# Digital_Trimmers.net
KiCad netlist of a schematic drawn in Altium Designer
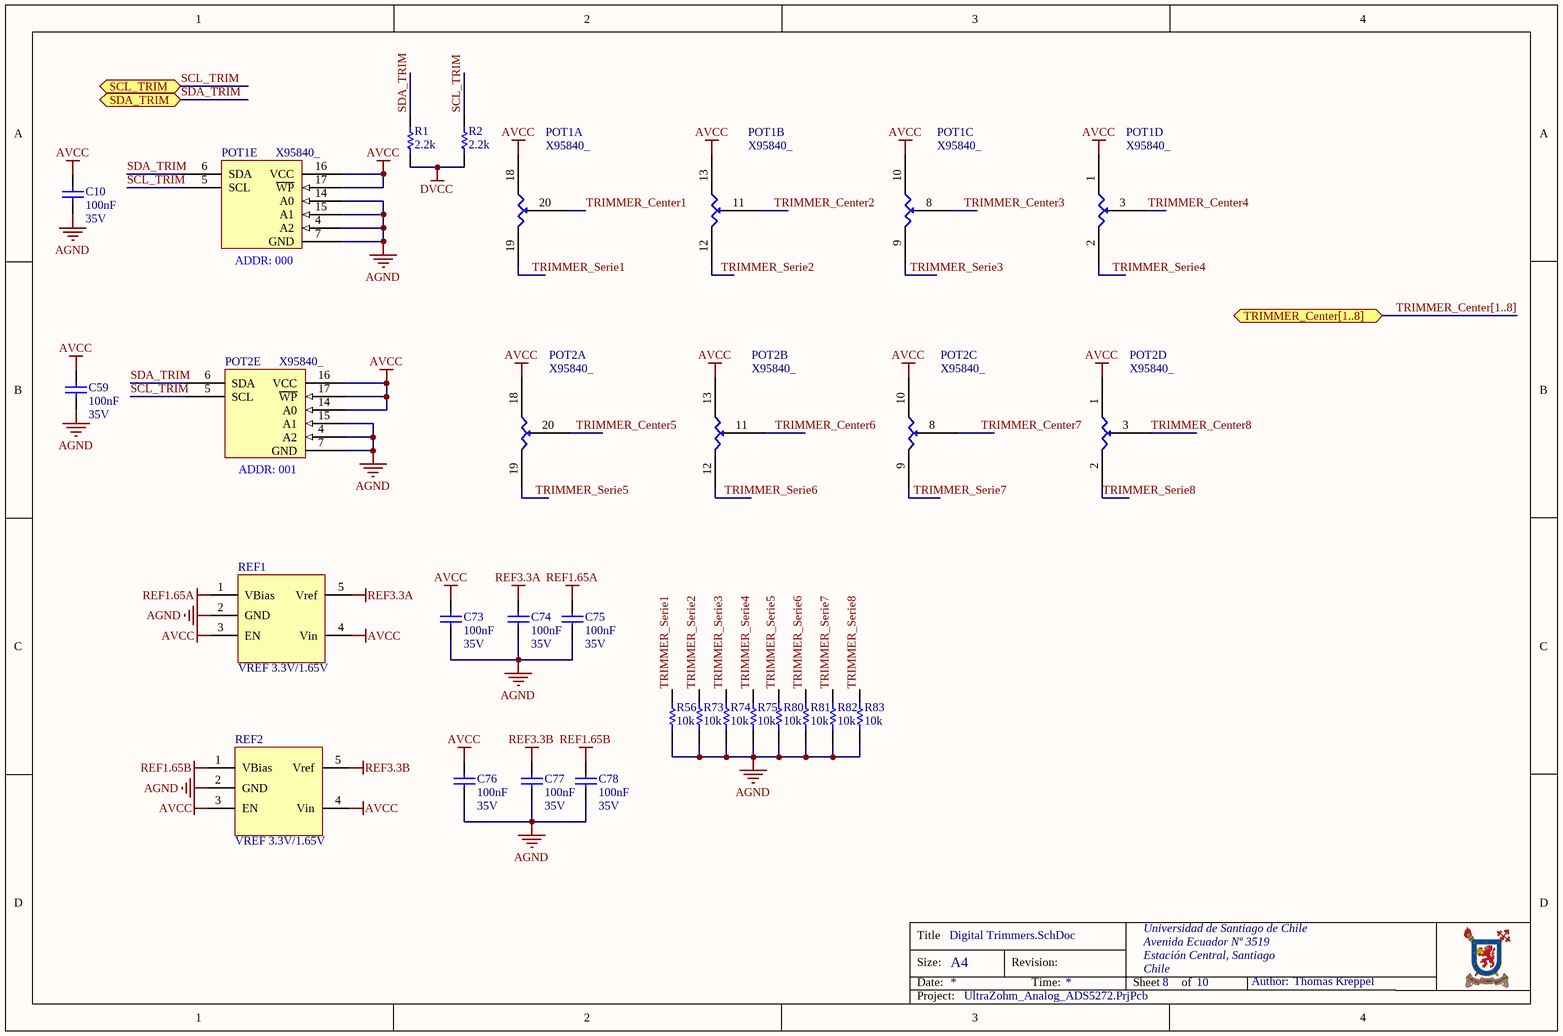
[diagram p0: Digital Trimmers.SchDoc]

(export (version "E")
  (design (tool "Eeschema 10.0.6"))
  (components
    (comp (ref "C10")
      (value "100nF")
      (footprint "CAP_0603")
      (description "Capacitor")
      (fields
        (field (name "MPN") "C0603C104M5RACTU")
        (field (name "MF") "KEMET")
        (field (name "VOLTAGE") "35V")
        (field (name "PUBLISHER") "Altium Limited")
      )
      (libsource (lib "Componentes_SOC") (part "Cap_0603"))
    )
    (comp (ref "C59")
      (value "100nF")
      (footprint "CAP_0603")
      (description "Capacitor")
      (fields
        (field (name "MPN") "C0603C104M5RACTU")
        (field (name "MF") "KEMET")
        (field (name "VOLTAGE") "35V")
        (field (name "PUBLISHER") "Altium Limited")
      )
      (libsource (lib "Componentes_SOC") (part "Cap_0603"))
    )
    (comp (ref "C73")
      (value "100nF")
      (footprint "CAP_0603")
      (description "Capacitor")
      (fields
        (field (name "MPN") "C0603C104M5RACTU")
        (field (name "MF") "KEMET")
        (field (name "VOLTAGE") "35V")
        (field (name "PUBLISHER") "Altium Limited")
      )
      (libsource (lib "Componentes_SOC") (part "Cap_0603"))
    )
    (comp (ref "C74")
      (value "100nF")
      (footprint "CAP_0603")
      (description "Capacitor")
      (fields
        (field (name "MPN") "C0603C104M5RACTU")
        (field (name "MF") "KEMET")
        (field (name "VOLTAGE") "35V")
        (field (name "PUBLISHER") "Altium Limited")
      )
      (libsource (lib "Componentes_SOC") (part "Cap_0603"))
    )
    (comp (ref "C75")
      (value "100nF")
      (footprint "CAP_0603")
      (description "Capacitor")
      (fields
        (field (name "MPN") "C0603C104M5RACTU")
        (field (name "MF") "KEMET")
        (field (name "VOLTAGE") "35V")
        (field (name "PUBLISHER") "Altium Limited")
      )
      (libsource (lib "Componentes_SOC") (part "Cap_0603"))
    )
    (comp (ref "C76")
      (value "100nF")
      (footprint "CAP_0603")
      (description "Capacitor")
      (fields
        (field (name "MPN") "C0603C104M5RACTU")
        (field (name "MF") "KEMET")
        (field (name "VOLTAGE") "35V")
        (field (name "PUBLISHER") "Altium Limited")
      )
      (libsource (lib "Componentes_SOC") (part "Cap_0603"))
    )
    (comp (ref "C77")
      (value "100nF")
      (footprint "CAP_0603")
      (description "Capacitor")
      (fields
        (field (name "MPN") "C0603C104M5RACTU")
        (field (name "MF") "KEMET")
        (field (name "VOLTAGE") "35V")
        (field (name "PUBLISHER") "Altium Limited")
      )
      (libsource (lib "Componentes_SOC") (part "Cap_0603"))
    )
    (comp (ref "C78")
      (value "100nF")
      (footprint "CAP_0603")
      (description "Capacitor")
      (fields
        (field (name "MPN") "C0603C104M5RACTU")
        (field (name "MF") "KEMET")
        (field (name "VOLTAGE") "35V")
        (field (name "PUBLISHER") "Altium Limited")
      )
      (libsource (lib "Componentes_SOC") (part "Cap_0603"))
    )
    (comp (ref "POT1")
      (value "X95840_")
      (footprint "TSSO6X6-G20/D6.6")
      (description "Digital Trimmer")
      (fields (field (name "MPN") "X95840WV20IZ-2.7") (field (name "MF") "Renesas Electronics"))
      (libsource (lib "Componentes_SOC") (part "X95840_"))
    )
    (comp (ref "POT2")
      (value "X95840_")
      (footprint "TSSO6X6-G20/D6.6")
      (description "Digital Trimmer")
      (fields (field (name "MPN") "X95840WV20IZ-2.7") (field (name "MF") "Renesas Electronics"))
      (libsource (lib "Componentes_SOC") (part "X95840_"))
    )
    (comp (ref "R1")
      (value "2.2k")
      (footprint "RES_0603")
      (fields
        (field (name "MPN") "RC0603FR-072K2L")
        (field (name "TOLERANCE") "1%")
        (field (name "PUBLISHER") "Altium Limited")
      )
      (libsource (lib "Componentes_SOC") (part "Res0603"))
    )
    (comp (ref "R2")
      (value "2.2k")
      (footprint "RES_0603")
      (fields
        (field (name "MPN") "RC0603FR-072K2L")
        (field (name "TOLERANCE") "1%")
        (field (name "PUBLISHER") "Altium Limited")
      )
      (libsource (lib "Componentes_SOC") (part "Res0603"))
    )
    (comp (ref "R56")
      (value "10k")
      (footprint "RES_0603")
      (fields (field (name "TOLERANCE") "1%") (field (name "PUBLISHER") "Altium Limited"))
      (libsource (lib "Componentes_SOC") (part "Res0603"))
    )
    (comp (ref "R73")
      (value "10k")
      (footprint "RES_0603")
      (fields (field (name "TOLERANCE") "1%") (field (name "PUBLISHER") "Altium Limited"))
      (libsource (lib "Componentes_SOC") (part "Res0603"))
    )
    (comp (ref "R74")
      (value "10k")
      (footprint "RES_0603")
      (fields (field (name "TOLERANCE") "1%") (field (name "PUBLISHER") "Altium Limited"))
      (libsource (lib "Componentes_SOC") (part "Res0603"))
    )
    (comp (ref "R75")
      (value "10k")
      (footprint "RES_0603")
      (fields (field (name "TOLERANCE") "1%") (field (name "PUBLISHER") "Altium Limited"))
      (libsource (lib "Componentes_SOC") (part "Res0603"))
    )
    (comp (ref "R80")
      (value "10k")
      (footprint "RES_0603")
      (fields (field (name "TOLERANCE") "1%") (field (name "PUBLISHER") "Altium Limited"))
      (libsource (lib "Componentes_SOC") (part "Res0603"))
    )
    (comp (ref "R81")
      (value "10k")
      (footprint "RES_0603")
      (fields (field (name "TOLERANCE") "1%") (field (name "PUBLISHER") "Altium Limited"))
      (libsource (lib "Componentes_SOC") (part "Res0603"))
    )
    (comp (ref "R82")
      (value "10k")
      (footprint "RES_0603")
      (fields (field (name "TOLERANCE") "1%") (field (name "PUBLISHER") "Altium Limited"))
      (libsource (lib "Componentes_SOC") (part "Res0603"))
    )
    (comp (ref "R83")
      (value "10k")
      (footprint "RES_0603")
      (fields (field (name "TOLERANCE") "1%") (field (name "PUBLISHER") "Altium Limited"))
      (libsource (lib "Componentes_SOC") (part "Res0603"))
    )
    (comp (ref "REF1")
      (value "VREF 3.3V/1.65V")
      (footprint "SOT-23-5")
      (libsource (lib "Componentes_SOC") (part "VREF 3.3V/1.65V"))
    )
    (comp (ref "REF2")
      (value "VREF 3.3V/1.65V")
      (footprint "SOT-23-5")
      (libsource (lib "Componentes_SOC") (part "VREF 3.3V/1.65V"))
    )
  )
  (nets
    (net (code "1") (name "/SCL_TRIM") (class "Default")
      (node (ref "POT1") (pin "5") (pinfunction "SCL_5") (pintype "passive"))
      (node (ref "POT2") (pin "5") (pinfunction "SCL_5") (pintype "passive"))
      (node (ref "R2") (pin "2") (pinfunction "2_2") (pintype "passive"))
    )
    (net (code "2") (name "/SDA_TRIM") (class "Default")
      (node (ref "POT1") (pin "6") (pinfunction "SDA_6") (pintype "passive"))
      (node (ref "POT2") (pin "6") (pinfunction "SDA_6") (pintype "passive"))
      (node (ref "R1") (pin "2") (pinfunction "2_2") (pintype "passive"))
    )
    (net (code "3") (name "/TRIMMER_Center1") (class "Default")
      (node (ref "POT1") (pin "20") (pinfunction "20_20") (pintype "passive"))
    )
    (net (code "4") (name "/TRIMMER_Center2") (class "Default")
      (node (ref "POT1") (pin "11") (pinfunction "RW1_11") (pintype "passive"))
    )
    (net (code "5") (name "/TRIMMER_Center3") (class "Default")
      (node (ref "POT1") (pin "8") (pinfunction "RW2_8") (pintype "passive"))
    )
    (net (code "6") (name "/TRIMMER_Center4") (class "Default")
      (node (ref "POT1") (pin "3") (pinfunction "RW3_3") (pintype "passive"))
    )
    (net (code "7") (name "/TRIMMER_Center5") (class "Default")
      (node (ref "POT2") (pin "20") (pinfunction "20_20") (pintype "passive"))
    )
    (net (code "8") (name "/TRIMMER_Center6") (class "Default")
      (node (ref "POT2") (pin "11") (pinfunction "RW1_11") (pintype "passive"))
    )
    (net (code "9") (name "/TRIMMER_Center7") (class "Default")
      (node (ref "POT2") (pin "8") (pinfunction "RW2_8") (pintype "passive"))
    )
    (net (code "10") (name "/TRIMMER_Center8") (class "Default")
      (node (ref "POT2") (pin "3") (pinfunction "RW3_3") (pintype "passive"))
    )
    (net (code "12") (name "/TRIMMER_Serie1") (class "Default")
      (node (ref "POT1") (pin "19") (pinfunction "19_19") (pintype "passive"))
      (node (ref "R56") (pin "2") (pinfunction "2_2") (pintype "passive"))
    )
    (net (code "13") (name "/TRIMMER_Serie2") (class "Default")
      (node (ref "POT1") (pin "12") (pinfunction "RL1_12") (pintype "passive"))
      (node (ref "R73") (pin "2") (pinfunction "2_2") (pintype "passive"))
    )
    (net (code "14") (name "/TRIMMER_Serie3") (class "Default")
      (node (ref "POT1") (pin "9") (pinfunction "RL2_9") (pintype "passive"))
      (node (ref "R74") (pin "2") (pinfunction "2_2") (pintype "passive"))
    )
    (net (code "15") (name "/TRIMMER_Serie4") (class "Default")
      (node (ref "POT1") (pin "2") (pinfunction "RL3_2") (pintype "passive"))
      (node (ref "R75") (pin "2") (pinfunction "2_2") (pintype "passive"))
    )
    (net (code "16") (name "/TRIMMER_Serie5") (class "Default")
      (node (ref "POT2") (pin "19") (pinfunction "19_19") (pintype "passive"))
      (node (ref "R80") (pin "2") (pinfunction "2_2") (pintype "passive"))
    )
    (net (code "17") (name "/TRIMMER_Serie6") (class "Default")
      (node (ref "POT2") (pin "12") (pinfunction "RL1_12") (pintype "passive"))
      (node (ref "R81") (pin "2") (pinfunction "2_2") (pintype "passive"))
    )
    (net (code "18") (name "/TRIMMER_Serie7") (class "Default")
      (node (ref "POT2") (pin "9") (pinfunction "RL2_9") (pintype "passive"))
      (node (ref "R82") (pin "2") (pinfunction "2_2") (pintype "passive"))
    )
    (net (code "19") (name "/TRIMMER_Serie8") (class "Default")
      (node (ref "POT2") (pin "2") (pinfunction "RL3_2") (pintype "passive"))
      (node (ref "R83") (pin "2") (pinfunction "2_2") (pintype "passive"))
    )
    (net (code "20") (name "AGND") (class "Default")
      (node (ref "C10") (pin "2") (pinfunction "2_2") (pintype "passive"))
      (node (ref "C59") (pin "2") (pinfunction "2_2") (pintype "passive"))
      (node (ref "C73") (pin "2") (pinfunction "2_2") (pintype "passive"))
      (node (ref "C74") (pin "2") (pinfunction "2_2") (pintype "passive"))
      (node (ref "C75") (pin "2") (pinfunction "2_2") (pintype "passive"))
      (node (ref "C76") (pin "2") (pinfunction "2_2") (pintype "passive"))
      (node (ref "C77") (pin "2") (pinfunction "2_2") (pintype "passive"))
      (node (ref "C78") (pin "2") (pinfunction "2_2") (pintype "passive"))
      (node (ref "POT1") (pin "14") (pinfunction "A0_14") (pintype "input"))
      (node (ref "POT1") (pin "15") (pinfunction "A1_15") (pintype "input"))
      (node (ref "POT1") (pin "4") (pinfunction "A2_4") (pintype "input"))
      (node (ref "POT1") (pin "7") (pinfunction "GND_7") (pintype "power_in"))
      (node (ref "POT2") (pin "15") (pinfunction "A1_15") (pintype "input"))
      (node (ref "POT2") (pin "4") (pinfunction "A2_4") (pintype "input"))
      (node (ref "POT2") (pin "7") (pinfunction "GND_7") (pintype "power_in"))
      (node (ref "R56") (pin "1") (pinfunction "1_1") (pintype "passive"))
      (node (ref "R73") (pin "1") (pinfunction "1_1") (pintype "passive"))
      (node (ref "R74") (pin "1") (pinfunction "1_1") (pintype "passive"))
      (node (ref "R75") (pin "1") (pinfunction "1_1") (pintype "passive"))
      (node (ref "R80") (pin "1") (pinfunction "1_1") (pintype "passive"))
      (node (ref "R81") (pin "1") (pinfunction "1_1") (pintype "passive"))
      (node (ref "R82") (pin "1") (pinfunction "1_1") (pintype "passive"))
      (node (ref "R83") (pin "1") (pinfunction "1_1") (pintype "passive"))
      (node (ref "REF1") (pin "2") (pinfunction "GND_2") (pintype "passive"))
      (node (ref "REF2") (pin "2") (pinfunction "GND_2") (pintype "passive"))
    )
    (net (code "21") (name "AVCC") (class "Default")
      (node (ref "C10") (pin "1") (pinfunction "1_1") (pintype "passive"))
      (node (ref "C59") (pin "1") (pinfunction "1_1") (pintype "passive"))
      (node (ref "C73") (pin "1") (pinfunction "1_1") (pintype "passive"))
      (node (ref "C76") (pin "1") (pinfunction "1_1") (pintype "passive"))
      (node (ref "POT1") (pin "1") (pinfunction "RH3_1") (pintype "passive"))
      (node (ref "POT1") (pin "10") (pinfunction "RH2_10") (pintype "passive"))
      (node (ref "POT1") (pin "13") (pinfunction "RH1_13") (pintype "passive"))
      (node (ref "POT1") (pin "16") (pinfunction "VCC_16") (pintype "power_in"))
      (node (ref "POT1") (pin "17") (pinfunction "~{WP}_17") (pintype "input"))
      (node (ref "POT1") (pin "18") (pinfunction "18_18") (pintype "passive"))
      (node (ref "POT2") (pin "1") (pinfunction "RH3_1") (pintype "passive"))
      (node (ref "POT2") (pin "10") (pinfunction "RH2_10") (pintype "passive"))
      (node (ref "POT2") (pin "13") (pinfunction "RH1_13") (pintype "passive"))
      (node (ref "POT2") (pin "14") (pinfunction "A0_14") (pintype "input"))
      (node (ref "POT2") (pin "16") (pinfunction "VCC_16") (pintype "power_in"))
      (node (ref "POT2") (pin "17") (pinfunction "~{WP}_17") (pintype "input"))
      (node (ref "POT2") (pin "18") (pinfunction "18_18") (pintype "passive"))
      (node (ref "REF1") (pin "3") (pinfunction "EN_3") (pintype "passive"))
      (node (ref "REF1") (pin "4") (pinfunction "Vin_4") (pintype "passive"))
      (node (ref "REF2") (pin "3") (pinfunction "EN_3") (pintype "passive"))
      (node (ref "REF2") (pin "4") (pinfunction "Vin_4") (pintype "passive"))
    )
    (net (code "22") (name "DVCC") (class "Default")
      (node (ref "R1") (pin "1") (pinfunction "1_1") (pintype "passive"))
      (node (ref "R2") (pin "1") (pinfunction "1_1") (pintype "passive"))
    )
    (net (code "23") (name "REF1.65A") (class "Default")
      (node (ref "C75") (pin "1") (pinfunction "1_1") (pintype "passive"))
      (node (ref "REF1") (pin "1") (pinfunction "VBias_1") (pintype "passive"))
    )
    (net (code "24") (name "REF1.65B") (class "Default")
      (node (ref "C78") (pin "1") (pinfunction "1_1") (pintype "passive"))
      (node (ref "REF2") (pin "1") (pinfunction "VBias_1") (pintype "passive"))
    )
    (net (code "25") (name "REF3.3A") (class "Default")
      (node (ref "C74") (pin "1") (pinfunction "1_1") (pintype "passive"))
      (node (ref "REF1") (pin "5") (pinfunction "Vref_5") (pintype "passive"))
    )
    (net (code "26") (name "REF3.3B") (class "Default")
      (node (ref "C77") (pin "1") (pinfunction "1_1") (pintype "passive"))
      (node (ref "REF2") (pin "5") (pinfunction "Vref_5") (pintype "passive"))
    )
  )
)
